# Analog_IN_block.net
KiCad netlist of a schematic drawn in Altium Designer
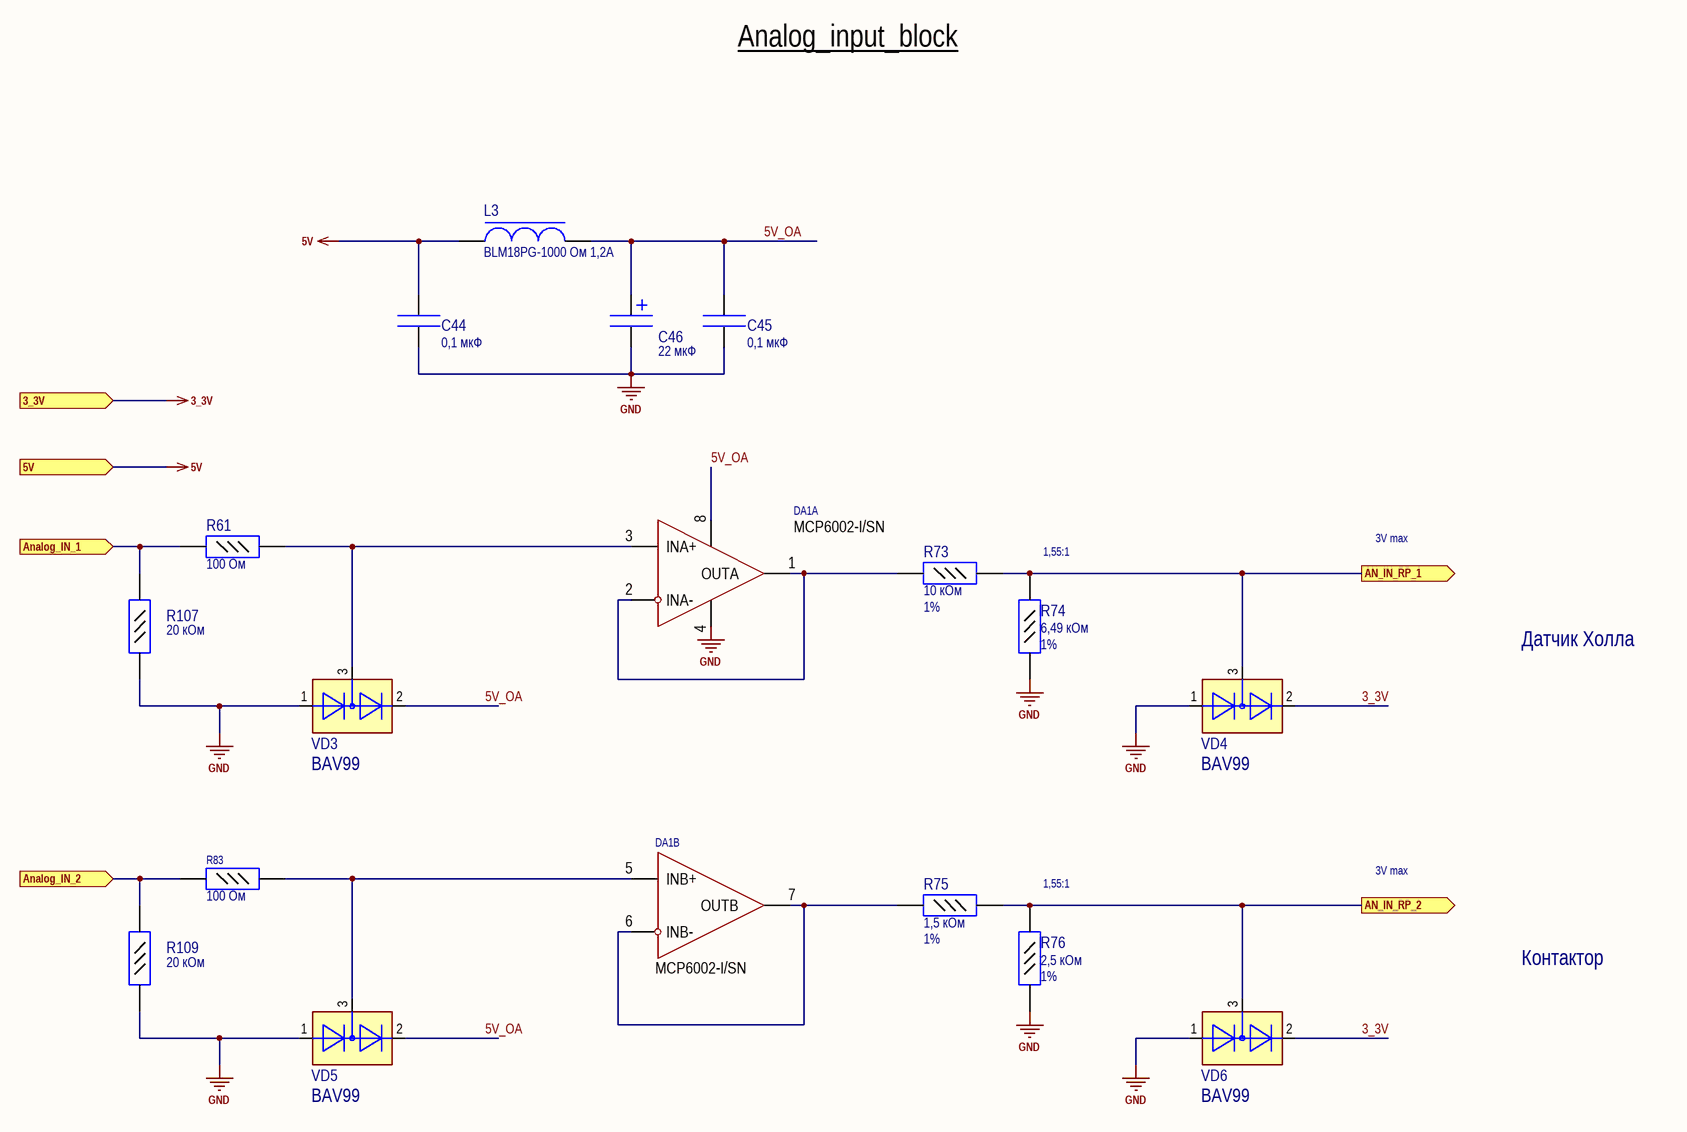
[diagram p0: Analog_IN_block.SchDoc]

(export (version "E")
  (design (tool "Eeschema 10.0.6"))
  (components
    (comp (ref "C44")
      (value "0,1 мкФ")
      (footprint "CC0603")
      (description "Чип конденсатор керамический")
      (fields (field (name "Comment") "CC0603-X7R-0,1 мкФ-20%-50В"))
      (libsource (lib "Конденсаторы") (part "CC0603-X7R-#-20%-50В"))
    )
    (comp (ref "C45")
      (value "0,1 мкФ")
      (footprint "CC0603")
      (description "Чип конденсатор керамический")
      (fields (field (name "Comment") "CC0603-X7R-0,1 мкФ-20%-50В"))
      (libsource (lib "Конденсаторы") (part "CC0603-X7R-#-20%-50В"))
    )
    (comp (ref "C46")
      (value "22 мкФ")
      (footprint "CT-D")
      (description "Чип конденсатор  танталовый")
      (fields (field (name "Comment") "CT-35V-22мкФ-±20%-D"))
      (libsource (lib "Конденсаторы") (part "CT-35V-#-±20%-D"))
    )
    (comp (ref "DA1")
      (value "MCP6002-I/SN")
      (footprint "8-SOIC")
      (description "Rail-to-Rail OP amplifier")
      (fields
        (field (name "MANUFACTURER") "Microchip")
        (field (name "VALUEMANUFACTURERPARTNUMBER") "IC op amplifier, Rail-to-Rail, 1 MHz, 1.8...6.0V, -40...+85°C, SO-8")
        (field (name "PARTNUMBER") "MCP6002-I/SN")
      )
      (libsource (lib "batmon_ICs") (part "MCP6002-I/SN"))
    )
    (comp (ref "L3")
      (value "BLM18PG-1000 Ом 1,2A")
      (footprint "CL0603")
      (description "Чип индуктивность подавления EMP")
      (libsource (lib "Индуктивности") (part "BLM18"))
    )
    (comp (ref "R61")
      (value "100 Ом")
      (footprint "CR0603")
      (description "Чип резистор")
      (fields (field (name "Comment") "CR0603-100 Ом-±5%"))
      (libsource (lib "Резисторы") (part "CR0603-#-±5%"))
    )
    (comp (ref "R73")
      (value "10 кОм")
      (footprint "CR0603")
      (description "Чип резистор")
      (fields (field (name "TOLERANCE") "1%") (field (name "Comment") "CR0603-10 кОм-±1%"))
      (libsource (lib "") (part "CR0603-#-±1%_1"))
    )
    (comp (ref "R74")
      (value "6,49 кОм")
      (footprint "CR0603")
      (description "Чип резистор")
      (fields (field (name "TOLERANCE") "1%") (field (name "Comment") "CR0603-6,49 кОм-±1%"))
      (libsource (lib "Резисторы") (part "CR0603-#-±1%"))
    )
    (comp (ref "R75")
      (value "1,5 кОм")
      (footprint "CR0603")
      (description "Чип резистор")
      (fields (field (name "TOLERANCE") "1%") (field (name "Comment") "CR0603-1,5 кОм-±1%"))
      (libsource (lib "") (part "CR0603-#-±1%_1"))
    )
    (comp (ref "R76")
      (value "2,5 кОм")
      (footprint "CR0603")
      (description "Чип резистор")
      (fields (field (name "TOLERANCE") "1%") (field (name "Comment") "CR0603-2,5 кОм-±1%"))
      (libsource (lib "Резисторы") (part "CR0603-#-±1%"))
    )
    (comp (ref "R83")
      (value "100 Ом")
      (footprint "CR0603")
      (description "Чип резистор")
      (fields (field (name "Comment") "CR0603-100 Ом-±5%"))
      (libsource (lib "Резисторы") (part "CR0603-#-±5%"))
    )
    (comp (ref "R107")
      (value "20 кОм")
      (footprint "CR0603")
      (description "Чип резистор")
      (fields (field (name "Comment") "CR0603-20 кОм-±5%"))
      (libsource (lib "") (part "CR0603-#-±5%_1"))
    )
    (comp (ref "R109")
      (value "20 кОм")
      (footprint "CR0603")
      (description "Чип резистор")
      (fields (field (name "Comment") "CR0603-20 кОм-±5%"))
      (libsource (lib "") (part "CR0603-#-±5%_1"))
    )
    (comp (ref "VD3")
      (value "BAV99")
      (footprint "SOT-23")
      (description "Диоды")
      (libsource (lib "Диоды") (part "BAV99"))
    )
    (comp (ref "VD4")
      (value "BAV99")
      (footprint "SOT-23")
      (description "Диоды")
      (libsource (lib "Диоды") (part "BAV99"))
    )
    (comp (ref "VD5")
      (value "BAV99")
      (footprint "SOT-23")
      (description "Диоды")
      (libsource (lib "Диоды") (part "BAV99"))
    )
    (comp (ref "VD6")
      (value "BAV99")
      (footprint "SOT-23")
      (description "Диоды")
      (libsource (lib "Диоды") (part "BAV99"))
    )
  )
  (nets
    (net (code "1") (name "/5V_OA") (class "Default")
      (node (ref "C45") (pin "1") (pinfunction "+_1") (pintype "passive"))
      (node (ref "C46") (pin "1") (pinfunction "+_1") (pintype "passive"))
      (node (ref "DA1") (pin "8") (pinfunction "V+_8") (pintype "power_in"))
      (node (ref "L3") (pin "2") (pinfunction "2_2") (pintype "passive"))
      (node (ref "VD3") (pin "2") (pintype "passive"))
      (node (ref "VD5") (pin "2") (pintype "passive"))
    )
    (net (code "2") (name "/AN_IN_RP_1") (class "Default")
      (node (ref "R73") (pin "2") (pinfunction "-_2") (pintype "passive"))
      (node (ref "R74") (pin "2") (pinfunction "-_2") (pintype "passive"))
      (node (ref "VD4") (pin "3") (pintype "passive"))
    )
    (net (code "3") (name "/AN_IN_RP_2") (class "Default")
      (node (ref "R75") (pin "2") (pinfunction "-_2") (pintype "passive"))
      (node (ref "R76") (pin "2") (pinfunction "-_2") (pintype "passive"))
      (node (ref "VD6") (pin "3") (pintype "passive"))
    )
    (net (code "4") (name "/Analog_IN_1") (class "Default")
      (node (ref "R107") (pin "2") (pinfunction "-_2") (pintype "passive"))
      (node (ref "R61") (pin "1") (pinfunction "+_1") (pintype "passive"))
    )
    (net (code "5") (name "/Analog_IN_2") (class "Default")
      (node (ref "R109") (pin "2") (pinfunction "-_2") (pintype "passive"))
      (node (ref "R83") (pin "1") (pinfunction "+_1") (pintype "passive"))
    )
    (net (code "6") (name "3_3V") (class "Default")
      (node (ref "VD4") (pin "2") (pintype "passive"))
      (node (ref "VD6") (pin "2") (pintype "passive"))
    )
    (net (code "7") (name "5V") (class "Default")
      (node (ref "C44") (pin "1") (pinfunction "+_1") (pintype "passive"))
      (node (ref "L3") (pin "1") (pinfunction "1_1") (pintype "passive"))
    )
    (net (code "8") (name "GND") (class "Default")
      (node (ref "C44") (pin "2") (pinfunction "-_2") (pintype "passive"))
      (node (ref "C45") (pin "2") (pinfunction "-_2") (pintype "passive"))
      (node (ref "C46") (pin "2") (pinfunction "-_2") (pintype "passive"))
      (node (ref "DA1") (pin "4") (pinfunction "V-_4") (pintype "power_in"))
      (node (ref "R107") (pin "1") (pinfunction "+_1") (pintype "passive"))
      (node (ref "R109") (pin "1") (pinfunction "+_1") (pintype "passive"))
      (node (ref "R74") (pin "1") (pinfunction "+_1") (pintype "passive"))
      (node (ref "R76") (pin "1") (pinfunction "+_1") (pintype "passive"))
      (node (ref "VD3") (pin "1") (pintype "passive"))
      (node (ref "VD4") (pin "1") (pintype "passive"))
      (node (ref "VD5") (pin "1") (pintype "passive"))
      (node (ref "VD6") (pin "1") (pintype "passive"))
    )
    (net (code "9") (name "Net-(DA1A-INA+)") (class "Default")
      (node (ref "DA1") (pin "3") (pinfunction "INA+_3") (pintype "passive"))
      (node (ref "R61") (pin "2") (pinfunction "-_2") (pintype "passive"))
      (node (ref "VD3") (pin "3") (pintype "passive"))
    )
    (net (code "10") (name "Net-(DA1A-INA-)") (class "Default")
      (node (ref "DA1") (pin "1") (pinfunction "OUTA_1") (pintype "power_in"))
      (node (ref "DA1") (pin "2") (pinfunction "INA-_2") (pintype "passive"))
      (node (ref "R73") (pin "1") (pinfunction "+_1") (pintype "passive"))
    )
    (net (code "11") (name "Net-(DA1B-INB+)") (class "Default")
      (node (ref "DA1") (pin "5") (pinfunction "INB+_5") (pintype "passive"))
      (node (ref "R83") (pin "2") (pinfunction "-_2") (pintype "passive"))
      (node (ref "VD5") (pin "3") (pintype "passive"))
    )
    (net (code "12") (name "Net-(DA1B-INB-)") (class "Default")
      (node (ref "DA1") (pin "6") (pinfunction "INB-_6") (pintype "passive"))
      (node (ref "DA1") (pin "7") (pinfunction "OUTB_7") (pintype "power_in"))
      (node (ref "R75") (pin "1") (pinfunction "+_1") (pintype "passive"))
    )
  )
)
